# Ex_EEPROM.net
KiCad netlist of a schematic drawn in EAGLE
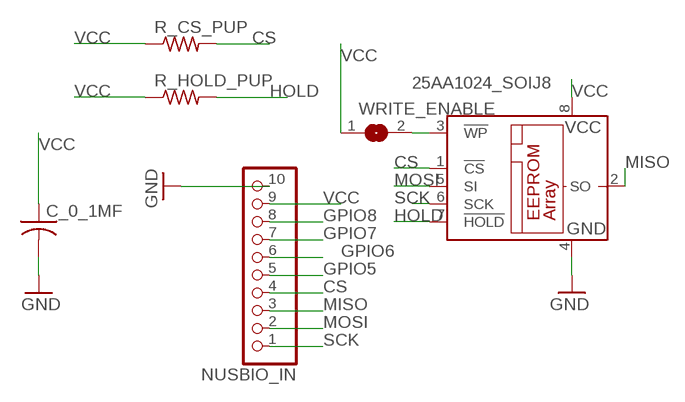
[diagram p0: schematic, sheet 1]

(export (version "E")
  (design (tool "Eeschema 10.0.6"))
  (components
    (comp (ref "25AA1024_SOIJ8")
      (value "25AA080SN")
      (footprint "eagle-import:SO-08")
      (fields (field (name "MF") "MICROCHIP") (field (name "MPN") "25AA080/SN"))
      (libsource (lib "eagle-import") (part "25SNAA080"))
    )
    (comp (ref "C_0_1MF")
      (value "C-USC1206")
      (footprint "eagle-import:C1206")
      (libsource (lib "eagle-import") (part "C-USC1206"))
    )
    (comp (ref "NUSBIO_IN")
      (value "PINHD-1X10")
      (footprint "eagle-import:1X10-BIG")
      (libsource (lib "eagle-import") (part "PINHD-1X10"))
    )
    (comp (ref "R_CS_PUP")
      (value "R-US_R1206")
      (footprint "eagle-import:R1206")
      (libsource (lib "eagle-import") (part "R-US_R1206"))
    )
    (comp (ref "R_HOLD_PUP")
      (value "R-US_R1206")
      (footprint "eagle-import:R1206")
      (libsource (lib "eagle-import") (part "R-US_R1206"))
    )
    (comp (ref "WRITE_ENABLE")
      (value "SOLDERJUMPERREFLOW")
      (footprint "eagle-import:SOLDERJUMPER_REFLOW")
      (libsource (lib "eagle-import") (part "SOLDERJUMPERREFLOW"))
    )
  )
  (nets
    (net (code "1") (name "/CS") (class "Default")
      (node (ref "25AA1024_SOIJ8") (pin "1") (pinfunction "~{CS}_1") (pintype "input"))
      (node (ref "NUSBIO_IN") (pin "4") (pinfunction "4_4") (pintype "passive"))
      (node (ref "R_CS_PUP") (pin "2") (pinfunction "2_2") (pintype "passive"))
    )
    (net (code "2") (name "/GPIO5") (class "Default")
      (node (ref "NUSBIO_IN") (pin "5") (pinfunction "5_5") (pintype "passive"))
    )
    (net (code "3") (name "/GPIO6") (class "Default")
      (node (ref "NUSBIO_IN") (pin "6") (pinfunction "6_6") (pintype "passive"))
    )
    (net (code "4") (name "/GPIO7") (class "Default")
      (node (ref "NUSBIO_IN") (pin "7") (pinfunction "7_7") (pintype "passive"))
    )
    (net (code "5") (name "/GPIO8") (class "Default")
      (node (ref "NUSBIO_IN") (pin "8") (pinfunction "8_8") (pintype "passive"))
    )
    (net (code "6") (name "/HOLD") (class "Default")
      (node (ref "25AA1024_SOIJ8") (pin "7") (pinfunction "~{HOLD}_7") (pintype "input"))
      (node (ref "R_HOLD_PUP") (pin "2") (pinfunction "2_2") (pintype "passive"))
    )
    (net (code "7") (name "/MISO") (class "Default")
      (node (ref "25AA1024_SOIJ8") (pin "2") (pinfunction "SO_2") (pintype "bidirectional"))
      (node (ref "NUSBIO_IN") (pin "3") (pinfunction "3_3") (pintype "passive"))
    )
    (net (code "8") (name "/MOSI") (class "Default")
      (node (ref "25AA1024_SOIJ8") (pin "5") (pinfunction "SI_5") (pintype "input"))
      (node (ref "NUSBIO_IN") (pin "2") (pinfunction "2_2") (pintype "passive"))
    )
    (net (code "9") (name "/SCK") (class "Default")
      (node (ref "25AA1024_SOIJ8") (pin "6") (pinfunction "SCK_6") (pintype "input"))
      (node (ref "NUSBIO_IN") (pin "1") (pinfunction "1_1") (pintype "passive"))
    )
    (net (code "10") (name "/VCC") (class "Default")
      (node (ref "25AA1024_SOIJ8") (pin "8") (pinfunction "VCC_8") (pintype "power_in"))
      (node (ref "C_0_1MF") (pin "1") (pinfunction "1_1") (pintype "passive"))
      (node (ref "NUSBIO_IN") (pin "9") (pinfunction "9_9") (pintype "passive"))
      (node (ref "R_CS_PUP") (pin "1") (pinfunction "1_1") (pintype "passive"))
      (node (ref "R_HOLD_PUP") (pin "1") (pinfunction "1_1") (pintype "passive"))
      (node (ref "WRITE_ENABLE") (pin "1") (pinfunction "1_1") (pintype "passive"))
    )
    (net (code "11") (name "GND") (class "Default")
      (node (ref "25AA1024_SOIJ8") (pin "4") (pinfunction "GND_4") (pintype "power_in"))
      (node (ref "C_0_1MF") (pin "2") (pinfunction "2_2") (pintype "passive"))
      (node (ref "NUSBIO_IN") (pin "10") (pinfunction "10_10") (pintype "passive"))
    )
    (net (code "12") (name "Net-(25AA1024_SOIJ8-~{WP})") (class "Default")
      (node (ref "25AA1024_SOIJ8") (pin "3") (pinfunction "~{WP}_3") (pintype "input"))
      (node (ref "WRITE_ENABLE") (pin "2") (pinfunction "2_2") (pintype "passive"))
    )
  )
)
